# d-ampsch.net
KiCad netlist of a schematic drawn in EAGLE
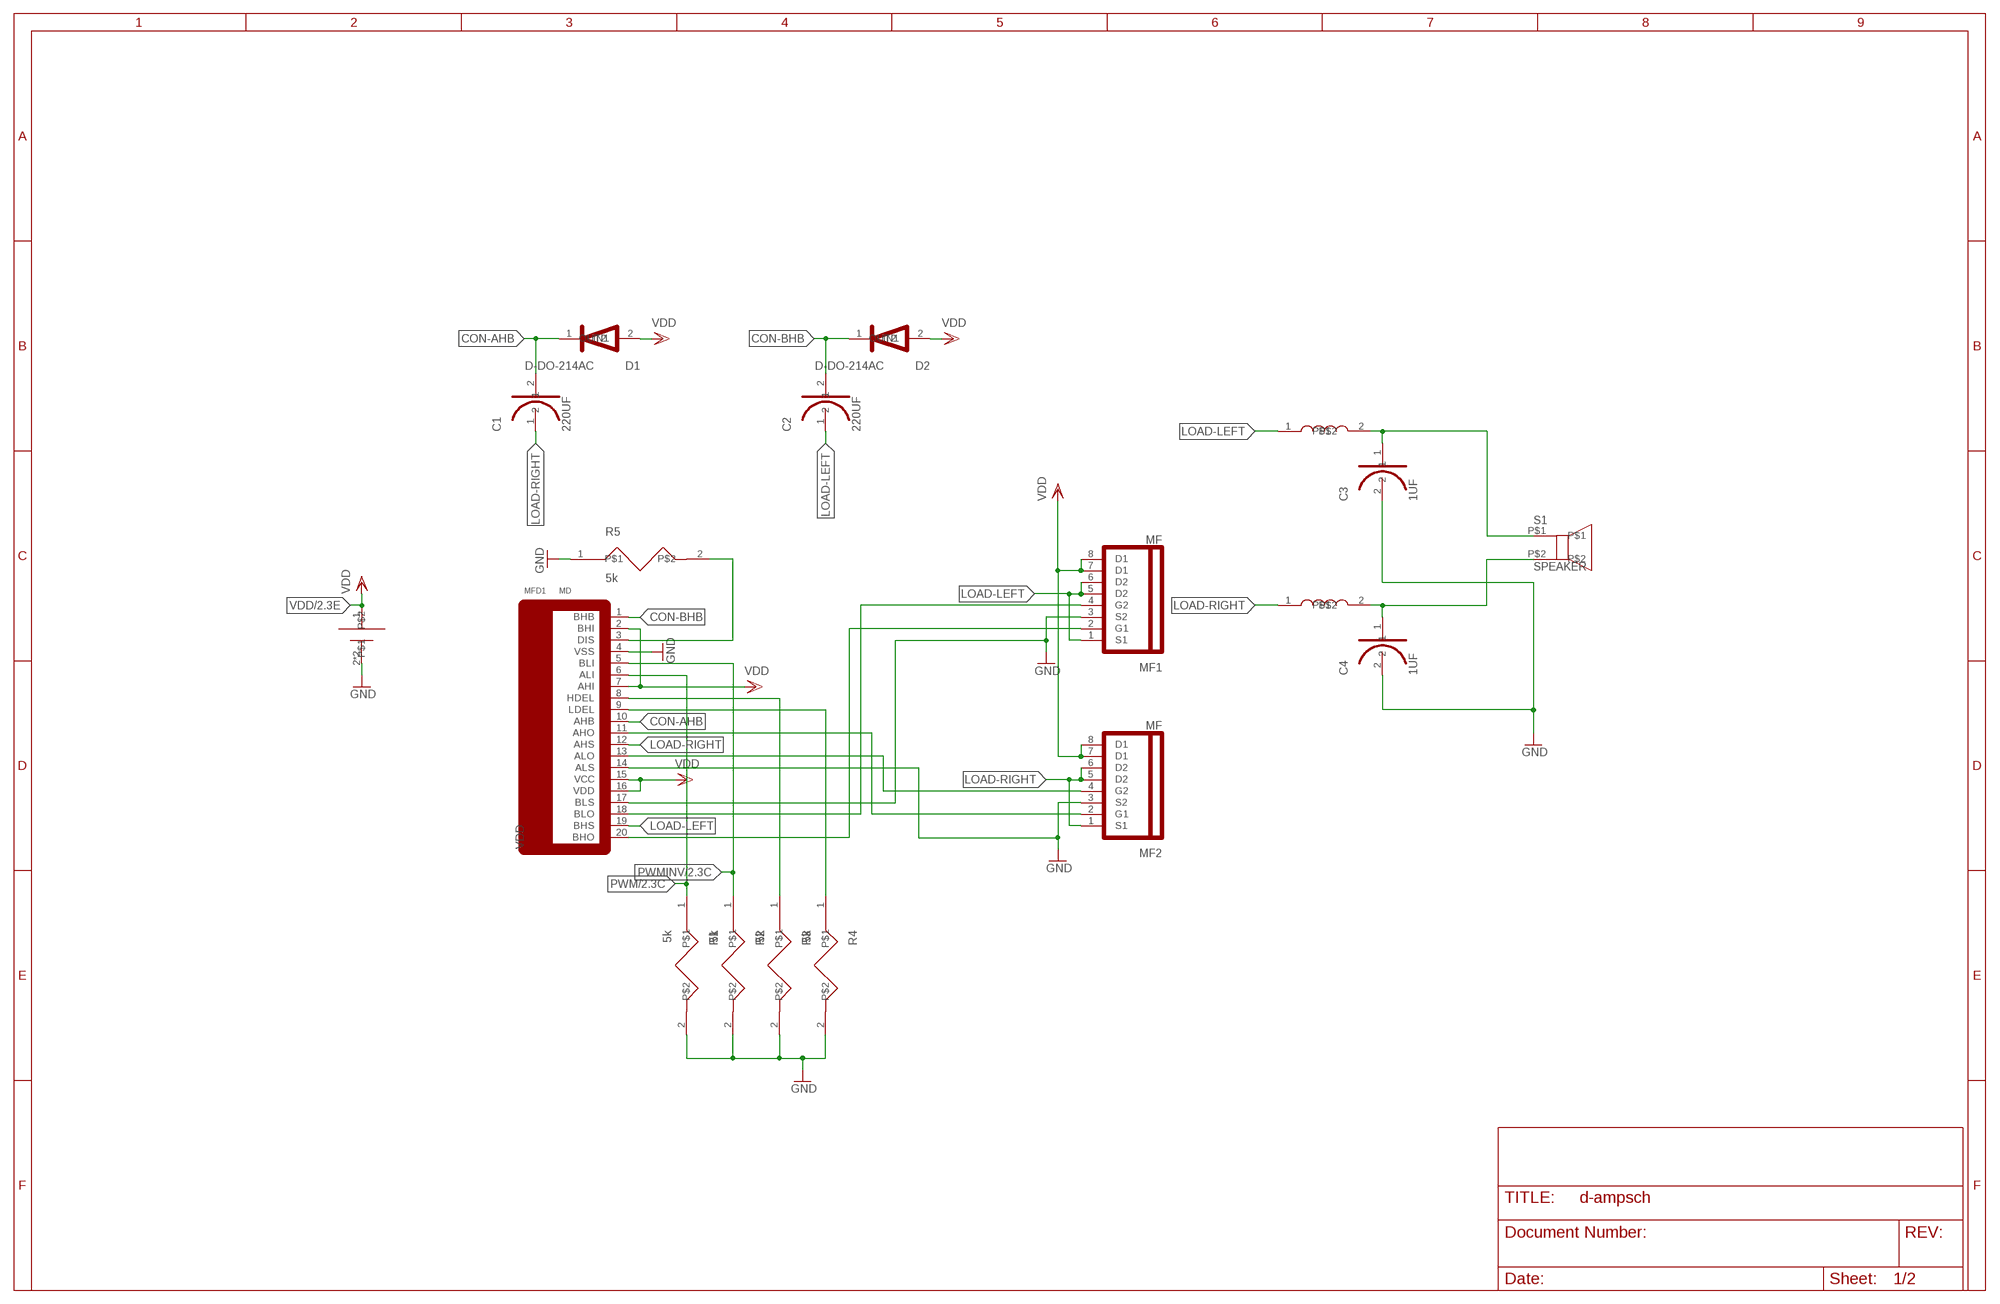
[diagram p0: schematic, sheet 1]
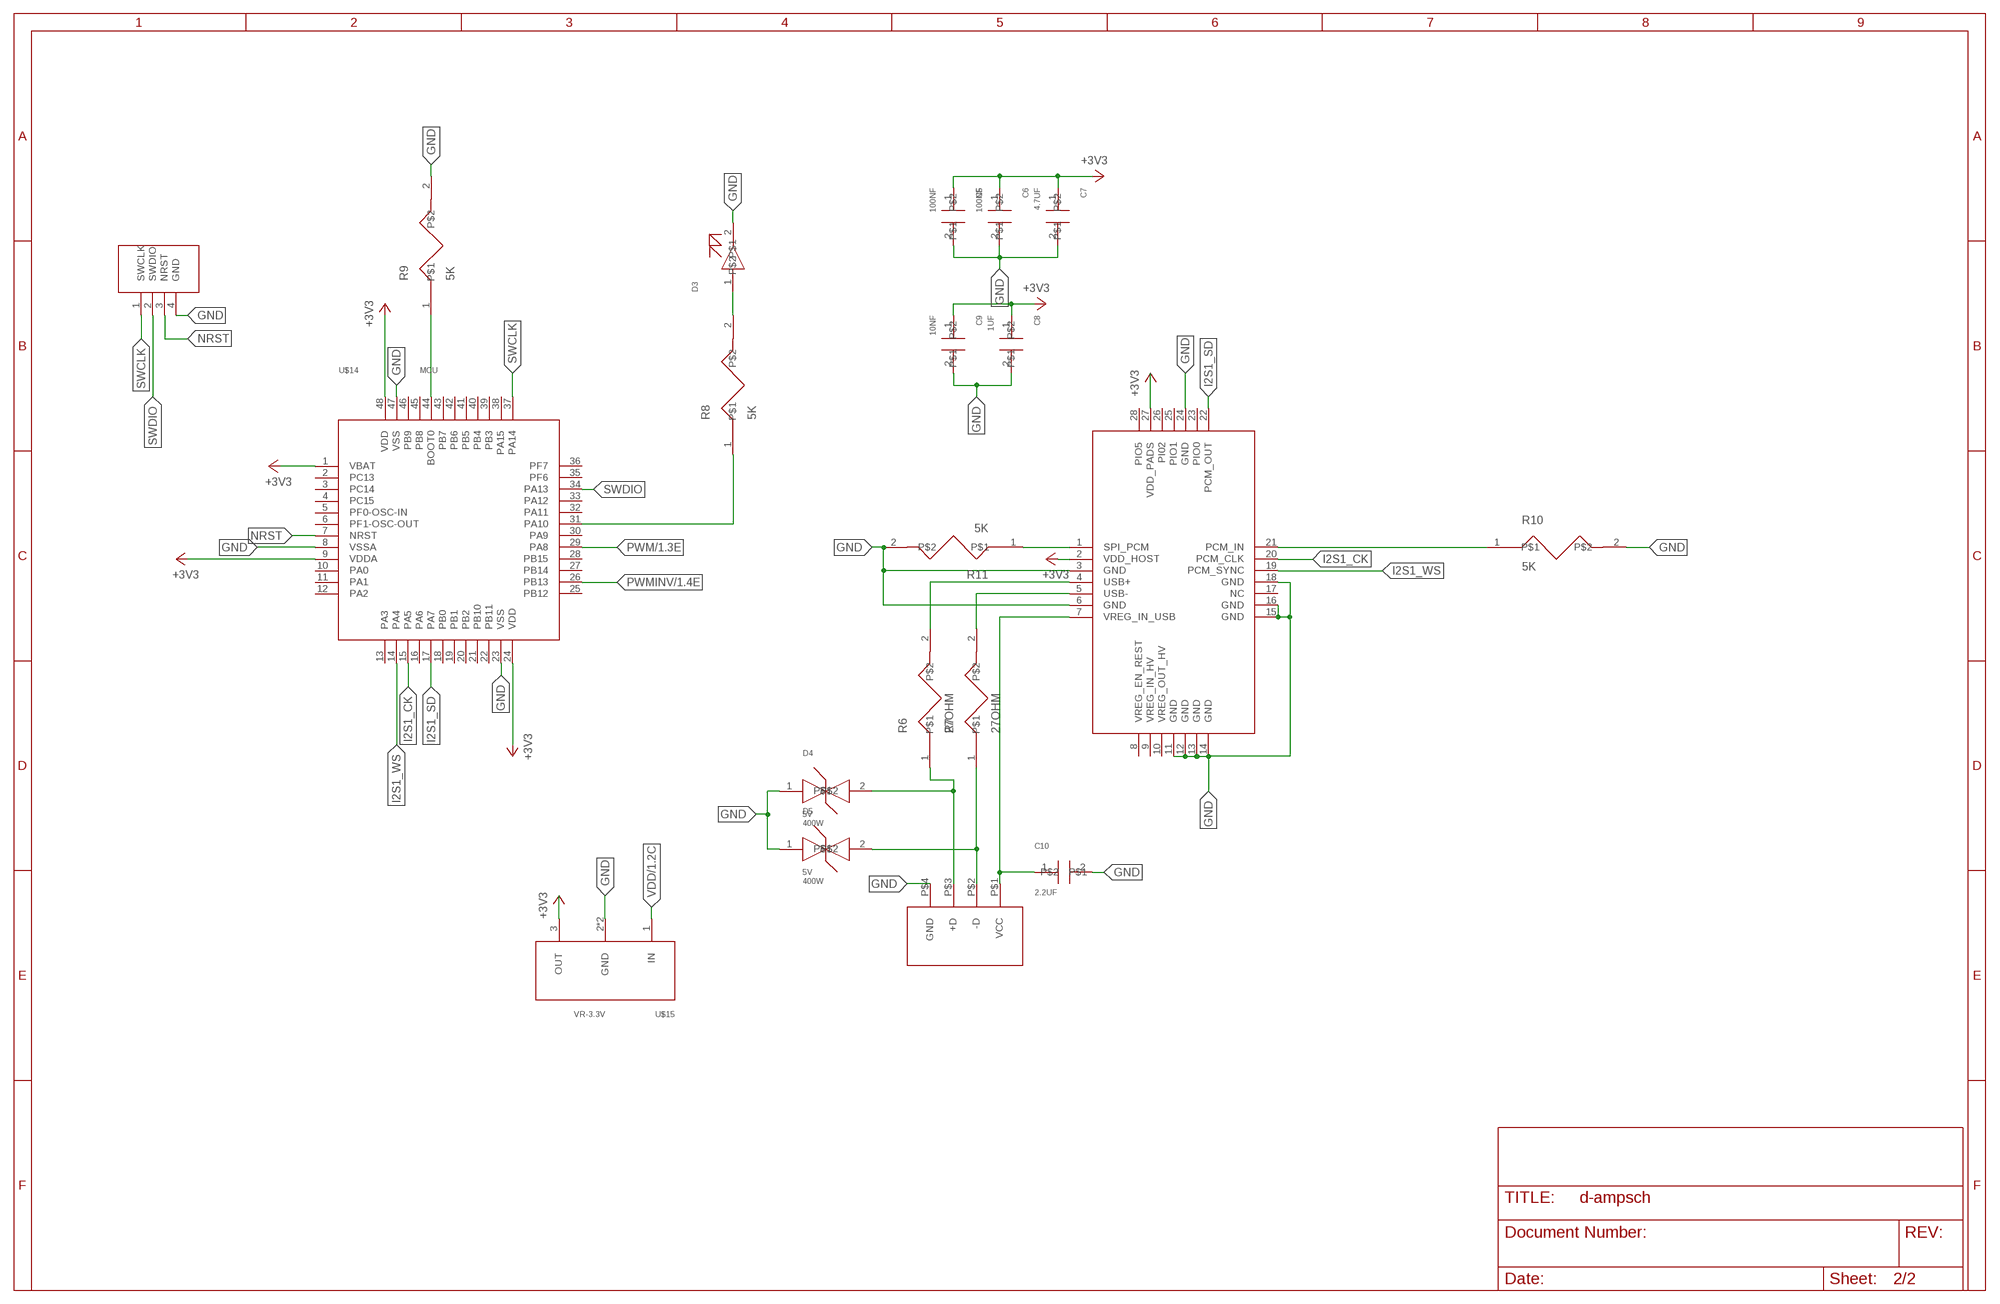
[diagram p1: schematic, sheet 2]

(export (version "E")
  (design (tool "Eeschema 10.0.6"))
  (components
    (comp (ref "C5")
      (value "100NF")
      (footprint "eagle-import:CAPC2012X70N")
      (libsource (lib "eagle-import") (part "C-100NF"))
    )
    (comp (ref "C6")
      (value "100NF")
      (footprint "eagle-import:CAPC2012X70N")
      (libsource (lib "eagle-import") (part "C-100NF"))
    )
    (comp (ref "C7")
      (value "4.7UF")
      (footprint "eagle-import:CAPC2012X145N")
      (libsource (lib "eagle-import") (part "C-4.7UFC-4.7UF"))
    )
    (comp (ref "C8")
      (value "1UF")
      (footprint "eagle-import:CAPC4532X70N")
      (libsource (lib "eagle-import") (part "C-1UF-NPC-1UF-NP"))
    )
    (comp (ref "C9")
      (value "10NF")
      (footprint "eagle-import:CAPC2012X145N")
      (libsource (lib "eagle-import") (part "C-10NF"))
    )
    (comp (ref "C10")
      (value "2.2UF")
      (footprint "eagle-import:CAPC1632X100N")
      (libsource (lib "eagle-import") (part "CAP-2.2UF"))
    )
    (comp (ref "D3")
      (value "LED_GREEN")
      (footprint "eagle-import:LEDC3333X200N")
      (libsource (lib "eagle-import") (part "LED_GREEN"))
    )
    (comp (ref "D4")
      (value "BI-DIR-5V")
      (footprint "eagle-import:DIOM5126X229N")
      (libsource (lib "eagle-import") (part "BI-DIR-5V"))
    )
    (comp (ref "D5")
      (value "BI-DIR-5V")
      (footprint "eagle-import:DIOM5126X229N")
      (libsource (lib "eagle-import") (part "BI-DIR-5V"))
    )
    (comp (ref "R6")
      (value "27OHM")
      (footprint "eagle-import:RESC2012X60N")
      (libsource (lib "eagle-import") (part "R-27OHM"))
    )
    (comp (ref "R7")
      (value "27OHM")
      (footprint "eagle-import:RESC2012X60N")
      (libsource (lib "eagle-import") (part "R-27OHM"))
    )
    (comp (ref "R8")
      (value "5K")
      (footprint "eagle-import:RESC2012X65N")
      (libsource (lib "eagle-import") (part "R-RN73C2A4K99B-5K"))
    )
    (comp (ref "R9")
      (value "5K")
      (footprint "eagle-import:RESC2012X65N")
      (libsource (lib "eagle-import") (part "R-RN73C2A4K99B-5K"))
    )
    (comp (ref "R10")
      (value "5K")
      (footprint "eagle-import:RESC2012X65N")
      (libsource (lib "eagle-import") (part "R-RN73C2A4K99B-5K"))
    )
    (comp (ref "R11")
      (value "5K")
      (footprint "eagle-import:RESC2012X65N")
      (libsource (lib "eagle-import") (part "R-RN73C2A4K99B-5K"))
    )
    (comp (ref "U$13")
      (value "BLUETOOTH")
      (footprint "eagle-import:QFN80P850X1285X175-42N")
      (libsource (lib "eagle-import") (part "BLUETOOTH"))
    )
    (comp (ref "U$14")
      (value "MCU")
      (footprint "eagle-import:QFP50P900X900X160-48N")
      (libsource (lib "eagle-import") (part "MCU"))
    )
    (comp (ref "U$15")
      (value "VR-3.3V")
      (footprint "eagle-import:SOT230P700X175-4N")
      (libsource (lib "eagle-import") (part "VR-3.3V"))
    )
    (comp (ref "U$23")
      (value "USB")
      (footprint "eagle-import:USB")
      (libsource (lib "eagle-import") (part "USB"))
    )
    (comp (ref "U$31")
      (value "PROGRAMCONN")
      (footprint "eagle-import:HDRV4W50P200_1X4_840X220X710B")
      (libsource (lib "eagle-import") (part "PROGRAMCONN"))
    )
    (comp (ref "C1")
      (value "220UF")
      (footprint "eagle-import:CAPAE1030X1050N")
      (libsource (lib "eagle-import") (part "C-EEEFK1H221P-220UF"))
    )
    (comp (ref "C2")
      (value "220UF")
      (footprint "eagle-import:CAPAE1030X1050N")
      (libsource (lib "eagle-import") (part "C-EEEFK1H221P-220UF"))
    )
    (comp (ref "C3")
      (value "1UF")
      (footprint "eagle-import:CAPAE430X610N")
      (libsource (lib "eagle-import") (part "C-EEEHB1H1R0R-1UF"))
    )
    (comp (ref "C4")
      (value "1UF")
      (footprint "eagle-import:CAPAE430X610N")
      (libsource (lib "eagle-import") (part "C-EEEHB1H1R0R-1UF"))
    )
    (comp (ref "D1")
      (value "D-DO-214AC")
      (footprint "eagle-import:SOD5226X220N")
      (libsource (lib "eagle-import") (part "D-DO-214AC"))
    )
    (comp (ref "D2")
      (value "D-DO-214AC")
      (footprint "eagle-import:SOD5226X220N")
      (libsource (lib "eagle-import") (part "D-DO-214AC"))
    )
    (comp (ref "MF1")
      (value "MF")
      (footprint "eagle-import:SOIC127P600X175-8N")
      (libsource (lib "eagle-import") (part "MF-PHN210T"))
    )
    (comp (ref "MF2")
      (value "MF")
      (footprint "eagle-import:SOIC127P600X175-8N")
      (libsource (lib "eagle-import") (part "MF-PHN210T"))
    )
    (comp (ref "MFD1")
      (value "MD")
      (footprint "eagle-import:SOIC127P1032X265-20N")
      (libsource (lib "eagle-import") (part "MD-HIP4081AIBZ"))
    )
    (comp (ref "R1")
      (value "5k")
      (footprint "eagle-import:RESC2012X65N")
      (libsource (lib "eagle-import") (part "R-RN73C2A4K99B-5K"))
    )
    (comp (ref "R2")
      (value "5k")
      (footprint "eagle-import:RESC2012X65N")
      (libsource (lib "eagle-import") (part "R-RN73C2A4K99B-5K"))
    )
    (comp (ref "R3")
      (value "5k")
      (footprint "eagle-import:RESC2012X65N")
      (libsource (lib "eagle-import") (part "R-RN73C2A4K99B-5K"))
    )
    (comp (ref "R4")
      (value "5k")
      (footprint "eagle-import:RESC2012X65N")
      (libsource (lib "eagle-import") (part "R-RN73C2A4K99B-5K"))
    )
    (comp (ref "R5")
      (value "5k")
      (footprint "eagle-import:RESC2012X65N")
      (libsource (lib "eagle-import") (part "R-RN73C2A4K99B-5K"))
    )
    (comp (ref "S1")
      (value "SPEAKER")
      (footprint "eagle-import:SPEAKER")
      (libsource (lib "eagle-import") (part "S-SPEAKER"))
    )
    (comp (ref "U$1")
      (value "B-BATTERYBATTERYCONN")
      (footprint "eagle-import:DIODFN1710X1680X1100-3N")
      (libsource (lib "eagle-import") (part "B-BATTERYBATTERYCONN"))
    )
    (comp (ref "U$21")
      (value "I-WURTH-10UH")
      (footprint "eagle-import:INDDFN2751X2800X1540-3N")
      (libsource (lib "eagle-import") (part "I-WURTH-10UH"))
    )
    (comp (ref "U$22")
      (value "I-WURTH-10UH")
      (footprint "eagle-import:INDDFN2751X2800X1540-3N")
      (libsource (lib "eagle-import") (part "I-WURTH-10UH"))
    )
  )
  (nets
    (net (code "1") (name "+3V3") (class "Default")
      (node (ref "C5") (pin "1") (pinfunction "P$1_1") (pintype "bidirectional"))
      (node (ref "C6") (pin "1") (pinfunction "P$1_1") (pintype "bidirectional"))
      (node (ref "C7") (pin "1") (pinfunction "P$1_1") (pintype "bidirectional"))
      (node (ref "C8") (pin "1") (pinfunction "P$1_1") (pintype "bidirectional"))
      (node (ref "C9") (pin "1") (pinfunction "P$1_1") (pintype "bidirectional"))
      (node (ref "U$13") (pin "2") (pinfunction "VDD_HOST_2") (pintype "bidirectional"))
      (node (ref "U$13") (pin "27") (pinfunction "VDD_PADS_27") (pintype "bidirectional"))
      (node (ref "U$14") (pin "1") (pinfunction "VBAT_1") (pintype "bidirectional"))
      (node (ref "U$14") (pin "24") (pinfunction "VDD_24") (pintype "bidirectional"))
      (node (ref "U$14") (pin "48") (pinfunction "VDD_48") (pintype "bidirectional"))
      (node (ref "U$14") (pin "9") (pinfunction "VDDA_9") (pintype "bidirectional"))
      (node (ref "U$15") (pin "3") (pinfunction "OUT_3") (pintype "bidirectional"))
    )
    (net (code "2") (name "CON-AHB") (class "Default")
      (node (ref "C1") (pin "2") (pinfunction "2_2") (pintype "bidirectional"))
      (node (ref "D1") (pin "1") (pinfunction "IN1_1") (pintype "bidirectional"))
      (node (ref "MFD1") (pin "10") (pinfunction "AHB_10") (pintype "bidirectional"))
    )
    (net (code "3") (name "CON-BHB") (class "Default")
      (node (ref "C2") (pin "2") (pinfunction "2_2") (pintype "bidirectional"))
      (node (ref "D2") (pin "1") (pinfunction "IN1_1") (pintype "bidirectional"))
      (node (ref "MFD1") (pin "1") (pinfunction "BHB_1") (pintype "bidirectional"))
    )
    (net (code "4") (name "GND") (class "Default")
      (node (ref "C10") (pin "2") (pinfunction "P$2_2") (pintype "bidirectional"))
      (node (ref "C3") (pin "2") (pinfunction "1_2") (pintype "bidirectional"))
      (node (ref "C4") (pin "2") (pinfunction "1_2") (pintype "bidirectional"))
      (node (ref "C5") (pin "2") (pinfunction "P$2_2") (pintype "bidirectional"))
      (node (ref "C6") (pin "2") (pinfunction "P$2_2") (pintype "bidirectional"))
      (node (ref "C7") (pin "2") (pinfunction "P$2_2") (pintype "bidirectional"))
      (node (ref "C8") (pin "2") (pinfunction "P$2_2") (pintype "bidirectional"))
      (node (ref "C9") (pin "2") (pinfunction "P$2_2") (pintype "bidirectional"))
      (node (ref "D3") (pin "2") (pinfunction "P$2_2") (pintype "bidirectional"))
      (node (ref "D4") (pin "1") (pinfunction "P$1_1") (pintype "bidirectional"))
      (node (ref "D5") (pin "1") (pinfunction "P$1_1") (pintype "bidirectional"))
      (node (ref "MF1") (pin "3") (pinfunction "S2_3") (pintype "bidirectional"))
      (node (ref "MF2") (pin "3") (pinfunction "S2_3") (pintype "bidirectional"))
      (node (ref "MFD1") (pin "14") (pinfunction "ALS_14") (pintype "bidirectional"))
      (node (ref "MFD1") (pin "17") (pinfunction "BLS_17") (pintype "bidirectional"))
      (node (ref "MFD1") (pin "4") (pinfunction "VSS_4") (pintype "bidirectional"))
      (node (ref "R1") (pin "2") (pinfunction "P$2_2") (pintype "bidirectional"))
      (node (ref "R10") (pin "2") (pinfunction "P$2_2") (pintype "bidirectional"))
      (node (ref "R11") (pin "2") (pinfunction "P$2_2") (pintype "bidirectional"))
      (node (ref "R2") (pin "2") (pinfunction "P$2_2") (pintype "bidirectional"))
      (node (ref "R3") (pin "2") (pinfunction "P$2_2") (pintype "bidirectional"))
      (node (ref "R4") (pin "2") (pinfunction "P$2_2") (pintype "bidirectional"))
      (node (ref "R5") (pin "1") (pinfunction "P$1_1") (pintype "bidirectional"))
      (node (ref "R9") (pin "2") (pinfunction "P$2_2") (pintype "bidirectional"))
      (node (ref "U$1") (pin "2") (pinfunction "P$2_2") (pintype "bidirectional"))
      (node (ref "U$1") (pin "3") (pinfunction "P$2_3") (pintype "bidirectional"))
      (node (ref "U$13") (pin "11") (pinfunction "GND_11") (pintype "bidirectional"))
      (node (ref "U$13") (pin "12") (pinfunction "GND_12") (pintype "bidirectional"))
      (node (ref "U$13") (pin "13") (pinfunction "GND_13") (pintype "bidirectional"))
      (node (ref "U$13") (pin "14") (pinfunction "GND_14") (pintype "bidirectional"))
      (node (ref "U$13") (pin "15") (pinfunction "GND_15") (pintype "bidirectional"))
      (node (ref "U$13") (pin "16") (pinfunction "GND_16") (pintype "bidirectional"))
      (node (ref "U$13") (pin "18") (pinfunction "GND_18") (pintype "bidirectional"))
      (node (ref "U$13") (pin "24") (pinfunction "GND_24") (pintype "bidirectional"))
      (node (ref "U$13") (pin "3") (pinfunction "GND_3") (pintype "bidirectional"))
      (node (ref "U$13") (pin "6") (pinfunction "GND_6") (pintype "bidirectional"))
      (node (ref "U$14") (pin "23") (pinfunction "VSS_23") (pintype "bidirectional"))
      (node (ref "U$14") (pin "47") (pinfunction "VSS_47") (pintype "bidirectional"))
      (node (ref "U$14") (pin "8") (pinfunction "VSSA_8") (pintype "bidirectional"))
      (node (ref "U$15") (pin "2") (pinfunction "GND_2") (pintype "bidirectional"))
      (node (ref "U$15") (pin "4") (pinfunction "GND_4") (pintype "bidirectional"))
      (node (ref "U$23") (pin "P$4") (pinfunction "GND_P$4") (pintype "bidirectional"))
      (node (ref "U$31") (pin "4") (pinfunction "GND_4") (pintype "bidirectional"))
    )
    (net (code "5") (name "I2S1_CK") (class "Default")
      (node (ref "U$13") (pin "20") (pinfunction "PCM_CLK_20") (pintype "bidirectional"))
      (node (ref "U$14") (pin "15") (pinfunction "PA5_15") (pintype "bidirectional"))
    )
    (net (code "6") (name "I2S1_SD") (class "Default")
      (node (ref "U$13") (pin "22") (pinfunction "PCM_OUT_22") (pintype "bidirectional"))
      (node (ref "U$14") (pin "17") (pinfunction "PA7_17") (pintype "bidirectional"))
    )
    (net (code "7") (name "I2S1_WS") (class "Default")
      (node (ref "U$13") (pin "19") (pinfunction "PCM_SYNC_19") (pintype "bidirectional"))
      (node (ref "U$14") (pin "14") (pinfunction "PA4_14") (pintype "bidirectional"))
    )
    (net (code "8") (name "LOAD-LEFT") (class "Default")
      (node (ref "C2") (pin "1") (pinfunction "1_1") (pintype "bidirectional"))
      (node (ref "MF1") (pin "1") (pinfunction "S1_1") (pintype "bidirectional"))
      (node (ref "MF1") (pin "5") (pinfunction "D2_5") (pintype "bidirectional"))
      (node (ref "MF1") (pin "6") (pinfunction "D2_6") (pintype "bidirectional"))
      (node (ref "MFD1") (pin "19") (pinfunction "BHS_19") (pintype "bidirectional"))
      (node (ref "U$21") (pin "1") (pinfunction "P$1_1") (pintype "bidirectional"))
    )
    (net (code "9") (name "LOAD-RIGHT") (class "Default")
      (node (ref "C1") (pin "1") (pinfunction "1_1") (pintype "bidirectional"))
      (node (ref "MF2") (pin "1") (pinfunction "S1_1") (pintype "bidirectional"))
      (node (ref "MF2") (pin "5") (pinfunction "D2_5") (pintype "bidirectional"))
      (node (ref "MF2") (pin "6") (pinfunction "D2_6") (pintype "bidirectional"))
      (node (ref "MFD1") (pin "12") (pinfunction "AHS_12") (pintype "bidirectional"))
      (node (ref "U$22") (pin "1") (pinfunction "P$1_1") (pintype "bidirectional"))
    )
    (net (code "10") (name "NRST") (class "Default")
      (node (ref "U$14") (pin "7") (pinfunction "NRST_7") (pintype "bidirectional"))
      (node (ref "U$31") (pin "3") (pinfunction "NRST_3") (pintype "bidirectional"))
    )
    (net (code "11") (name "Net-(C3-2)") (class "Default")
      (node (ref "C3") (pin "1") (pinfunction "2_1") (pintype "bidirectional"))
      (node (ref "S1") (pin "P$1") (pinfunction "P$1_P$1") (pintype "bidirectional"))
      (node (ref "U$21") (pin "2") (pinfunction "P$2_2") (pintype "bidirectional"))
    )
    (net (code "12") (name "Net-(C4-2)") (class "Default")
      (node (ref "C4") (pin "1") (pinfunction "2_1") (pintype "bidirectional"))
      (node (ref "S1") (pin "P$2") (pinfunction "P$2_P$2") (pintype "bidirectional"))
      (node (ref "U$22") (pin "2") (pinfunction "P$2_2") (pintype "bidirectional"))
    )
    (net (code "13") (name "Net-(C10-P$1)") (class "Default")
      (node (ref "C10") (pin "1") (pinfunction "P$1_1") (pintype "bidirectional"))
      (node (ref "U$13") (pin "7") (pinfunction "VREG_IN_USB_7") (pintype "bidirectional"))
      (node (ref "U$23") (pin "P$1") (pinfunction "VCC_P$1") (pintype "bidirectional"))
    )
    (net (code "14") (name "Net-(D3-P$1)") (class "Default")
      (node (ref "D3") (pin "1") (pinfunction "P$1_1") (pintype "bidirectional"))
      (node (ref "R8") (pin "2") (pinfunction "P$2_2") (pintype "bidirectional"))
    )
    (net (code "15") (name "Net-(D4-P$2)") (class "Default")
      (node (ref "D4") (pin "2") (pinfunction "P$2_2") (pintype "bidirectional"))
      (node (ref "R6") (pin "1") (pinfunction "P$1_1") (pintype "bidirectional"))
      (node (ref "U$23") (pin "P$3") (pinfunction "+D_P$3") (pintype "bidirectional"))
    )
    (net (code "16") (name "Net-(D5-P$2)") (class "Default")
      (node (ref "D5") (pin "2") (pinfunction "P$2_2") (pintype "bidirectional"))
      (node (ref "R7") (pin "1") (pinfunction "P$1_1") (pintype "bidirectional"))
      (node (ref "U$23") (pin "P$2") (pinfunction "-D_P$2") (pintype "bidirectional"))
    )
    (net (code "17") (name "Net-(MF1-G1)") (class "Default")
      (node (ref "MF1") (pin "2") (pinfunction "G1_2") (pintype "bidirectional"))
      (node (ref "MFD1") (pin "20") (pinfunction "BHO_20") (pintype "bidirectional"))
    )
    (net (code "18") (name "Net-(MF1-G2)") (class "Default")
      (node (ref "MF1") (pin "4") (pinfunction "G2_4") (pintype "bidirectional"))
      (node (ref "MFD1") (pin "18") (pinfunction "BLO_18") (pintype "bidirectional"))
    )
    (net (code "19") (name "Net-(MF2-G1)") (class "Default")
      (node (ref "MF2") (pin "2") (pinfunction "G1_2") (pintype "bidirectional"))
      (node (ref "MFD1") (pin "11") (pinfunction "AHO_11") (pintype "bidirectional"))
    )
    (net (code "20") (name "Net-(MF2-G2)") (class "Default")
      (node (ref "MF2") (pin "4") (pinfunction "G2_4") (pintype "bidirectional"))
      (node (ref "MFD1") (pin "13") (pinfunction "ALO_13") (pintype "bidirectional"))
    )
    (net (code "21") (name "Net-(MFD1-DIS)") (class "Default")
      (node (ref "MFD1") (pin "3") (pinfunction "DIS_3") (pintype "bidirectional"))
      (node (ref "R5") (pin "2") (pinfunction "P$2_2") (pintype "bidirectional"))
    )
    (net (code "22") (name "Net-(MFD1-HDEL)") (class "Default")
      (node (ref "MFD1") (pin "8") (pinfunction "HDEL_8") (pintype "bidirectional"))
      (node (ref "R3") (pin "1") (pinfunction "P$1_1") (pintype "bidirectional"))
    )
    (net (code "23") (name "Net-(MFD1-LDEL)") (class "Default")
      (node (ref "MFD1") (pin "9") (pinfunction "LDEL_9") (pintype "bidirectional"))
      (node (ref "R4") (pin "1") (pinfunction "P$1_1") (pintype "bidirectional"))
    )
    (net (code "24") (name "Net-(R6-P$2)") (class "Default")
      (node (ref "R6") (pin "2") (pinfunction "P$2_2") (pintype "bidirectional"))
      (node (ref "U$13") (pin "4") (pinfunction "USB+_4") (pintype "bidirectional"))
    )
    (net (code "25") (name "Net-(R7-P$2)") (class "Default")
      (node (ref "R7") (pin "2") (pinfunction "P$2_2") (pintype "bidirectional"))
      (node (ref "U$13") (pin "5") (pinfunction "USB-_5") (pintype "bidirectional"))
    )
    (net (code "26") (name "Net-(R8-P$1)") (class "Default")
      (node (ref "R8") (pin "1") (pinfunction "P$1_1") (pintype "bidirectional"))
      (node (ref "U$14") (pin "31") (pinfunction "PA10_31") (pintype "bidirectional"))
    )
    (net (code "27") (name "Net-(R9-P$1)") (class "Default")
      (node (ref "R9") (pin "1") (pinfunction "P$1_1") (pintype "bidirectional"))
      (node (ref "U$14") (pin "44") (pinfunction "BOOT0_44") (pintype "bidirectional"))
    )
    (net (code "28") (name "Net-(R10-P$1)") (class "Default")
      (node (ref "R10") (pin "1") (pinfunction "P$1_1") (pintype "bidirectional"))
      (node (ref "U$13") (pin "21") (pinfunction "PCM_IN_21") (pintype "bidirectional"))
    )
    (net (code "29") (name "Net-(R11-P$1)") (class "Default")
      (node (ref "R11") (pin "1") (pinfunction "P$1_1") (pintype "bidirectional"))
      (node (ref "U$13") (pin "1") (pinfunction "SPI_PCM_1") (pintype "bidirectional"))
    )
    (net (code "30") (name "PWM") (class "Default")
      (node (ref "MFD1") (pin "6") (pinfunction "ALI_6") (pintype "bidirectional"))
      (node (ref "R1") (pin "1") (pinfunction "P$1_1") (pintype "bidirectional"))
      (node (ref "U$14") (pin "29") (pinfunction "PA8_29") (pintype "bidirectional"))
    )
    (net (code "31") (name "PWMINV") (class "Default")
      (node (ref "MFD1") (pin "5") (pinfunction "BLI_5") (pintype "bidirectional"))
      (node (ref "R2") (pin "1") (pinfunction "P$1_1") (pintype "bidirectional"))
      (node (ref "U$14") (pin "26") (pinfunction "PB13_26") (pintype "bidirectional"))
    )
    (net (code "32") (name "SWCLK") (class "Default")
      (node (ref "U$14") (pin "37") (pinfunction "PA14_37") (pintype "bidirectional"))
      (node (ref "U$31") (pin "1") (pinfunction "SWCLK_1") (pintype "bidirectional"))
    )
    (net (code "33") (name "SWDIO") (class "Default")
      (node (ref "U$14") (pin "34") (pinfunction "PA13_34") (pintype "bidirectional"))
      (node (ref "U$31") (pin "2") (pinfunction "SWDIO_2") (pintype "bidirectional"))
    )
    (net (code "34") (name "VDD") (class "Default")
      (node (ref "D1") (pin "2") (pinfunction "OUT2_2") (pintype "bidirectional"))
      (node (ref "D2") (pin "2") (pinfunction "OUT2_2") (pintype "bidirectional"))
      (node (ref "MF1") (pin "7") (pinfunction "D1_7") (pintype "bidirectional"))
      (node (ref "MF1") (pin "8") (pinfunction "D1_8") (pintype "bidirectional"))
      (node (ref "MF2") (pin "7") (pinfunction "D1_7") (pintype "bidirectional"))
      (node (ref "MF2") (pin "8") (pinfunction "D1_8") (pintype "bidirectional"))
      (node (ref "MFD1") (pin "15") (pinfunction "VCC_15") (pintype "bidirectional"))
      (node (ref "MFD1") (pin "16") (pinfunction "VDD_16") (pintype "bidirectional"))
      (node (ref "MFD1") (pin "2") (pinfunction "BHI_2") (pintype "bidirectional"))
      (node (ref "MFD1") (pin "7") (pinfunction "AHI_7") (pintype "bidirectional"))
      (node (ref "U$1") (pin "1") (pinfunction "P$1_1") (pintype "bidirectional"))
      (node (ref "U$15") (pin "1") (pinfunction "IN_1") (pintype "bidirectional"))
    )
    (net (code "35") (name "unconnected-(U$13-NC-Pad17)") (class "Default")
      (node (ref "U$13") (pin "17") (pinfunction "NC_17") (pintype "bidirectional"))
    )
    (net (code "36") (name "unconnected-(U$13-PI02-Pad26)") (class "Default")
      (node (ref "U$13") (pin "26") (pinfunction "PI02_26") (pintype "bidirectional"))
    )
    (net (code "37") (name "unconnected-(U$13-PIO0-Pad23)") (class "Default")
      (node (ref "U$13") (pin "23") (pinfunction "PIO0_23") (pintype "bidirectional"))
    )
    (net (code "38") (name "unconnected-(U$13-PIO1-Pad25)") (class "Default")
      (node (ref "U$13") (pin "25") (pinfunction "PIO1_25") (pintype "bidirectional"))
    )
    (net (code "39") (name "unconnected-(U$13-PIO5-Pad28)") (class "Default")
      (node (ref "U$13") (pin "28") (pinfunction "PIO5_28") (pintype "bidirectional"))
    )
    (net (code "40") (name "unconnected-(U$13-VREG_EN_REST-Pad8)") (class "Default")
      (node (ref "U$13") (pin "8") (pinfunction "VREG_EN_REST_8") (pintype "bidirectional"))
    )
    (net (code "41") (name "unconnected-(U$13-VREG_IN_HV-Pad9)") (class "Default")
      (node (ref "U$13") (pin "9") (pinfunction "VREG_IN_HV_9") (pintype "bidirectional"))
    )
    (net (code "42") (name "unconnected-(U$13-VREG_OUT_HV-Pad10)") (class "Default")
      (node (ref "U$13") (pin "10") (pinfunction "VREG_OUT_HV_10") (pintype "bidirectional"))
    )
    (net (code "43") (name "unconnected-(U$14-PA0-Pad10)") (class "Default")
      (node (ref "U$14") (pin "10") (pinfunction "PA0_10") (pintype "bidirectional"))
    )
    (net (code "44") (name "unconnected-(U$14-PA1-Pad11)") (class "Default")
      (node (ref "U$14") (pin "11") (pinfunction "PA1_11") (pintype "bidirectional"))
    )
    (net (code "45") (name "unconnected-(U$14-PA2-Pad12)") (class "Default")
      (node (ref "U$14") (pin "12") (pinfunction "PA2_12") (pintype "bidirectional"))
    )
    (net (code "46") (name "unconnected-(U$14-PA3-Pad13)") (class "Default")
      (node (ref "U$14") (pin "13") (pinfunction "PA3_13") (pintype "bidirectional"))
    )
    (net (code "47") (name "unconnected-(U$14-PA6-Pad16)") (class "Default")
      (node (ref "U$14") (pin "16") (pinfunction "PA6_16") (pintype "bidirectional"))
    )
    (net (code "48") (name "unconnected-(U$14-PA9-Pad30)") (class "Default")
      (node (ref "U$14") (pin "30") (pinfunction "PA9_30") (pintype "bidirectional"))
    )
    (net (code "49") (name "unconnected-(U$14-PA11-Pad32)") (class "Default")
      (node (ref "U$14") (pin "32") (pinfunction "PA11_32") (pintype "bidirectional"))
    )
    (net (code "50") (name "unconnected-(U$14-PA12-Pad33)") (class "Default")
      (node (ref "U$14") (pin "33") (pinfunction "PA12_33") (pintype "bidirectional"))
    )
    (net (code "51") (name "unconnected-(U$14-PA15-Pad38)") (class "Default")
      (node (ref "U$14") (pin "38") (pinfunction "PA15_38") (pintype "bidirectional"))
    )
    (net (code "52") (name "unconnected-(U$14-PB0-Pad18)") (class "Default")
      (node (ref "U$14") (pin "18") (pinfunction "PB0_18") (pintype "bidirectional"))
    )
    (net (code "53") (name "unconnected-(U$14-PB1-Pad19)") (class "Default")
      (node (ref "U$14") (pin "19") (pinfunction "PB1_19") (pintype "bidirectional"))
    )
    (net (code "54") (name "unconnected-(U$14-PB2-Pad20)") (class "Default")
      (node (ref "U$14") (pin "20") (pinfunction "PB2_20") (pintype "bidirectional"))
    )
    (net (code "55") (name "unconnected-(U$14-PB3-Pad39)") (class "Default")
      (node (ref "U$14") (pin "39") (pinfunction "PB3_39") (pintype "bidirectional"))
    )
    (net (code "56") (name "unconnected-(U$14-PB4-Pad40)") (class "Default")
      (node (ref "U$14") (pin "40") (pinfunction "PB4_40") (pintype "bidirectional"))
    )
    (net (code "57") (name "unconnected-(U$14-PB5-Pad41)") (class "Default")
      (node (ref "U$14") (pin "41") (pinfunction "PB5_41") (pintype "bidirectional"))
    )
    (net (code "58") (name "unconnected-(U$14-PB6-Pad42)") (class "Default")
      (node (ref "U$14") (pin "42") (pinfunction "PB6_42") (pintype "bidirectional"))
    )
    (net (code "59") (name "unconnected-(U$14-PB7-Pad43)") (class "Default")
      (node (ref "U$14") (pin "43") (pinfunction "PB7_43") (pintype "bidirectional"))
    )
    (net (code "60") (name "unconnected-(U$14-PB8-Pad45)") (class "Default")
      (node (ref "U$14") (pin "45") (pinfunction "PB8_45") (pintype "bidirectional"))
    )
    (net (code "61") (name "unconnected-(U$14-PB9-Pad46)") (class "Default")
      (node (ref "U$14") (pin "46") (pinfunction "PB9_46") (pintype "bidirectional"))
    )
    (net (code "62") (name "unconnected-(U$14-PB10-Pad21)") (class "Default")
      (node (ref "U$14") (pin "21") (pinfunction "PB10_21") (pintype "bidirectional"))
    )
    (net (code "63") (name "unconnected-(U$14-PB11-Pad22)") (class "Default")
      (node (ref "U$14") (pin "22") (pinfunction "PB11_22") (pintype "bidirectional"))
    )
    (net (code "64") (name "unconnected-(U$14-PB12-Pad25)") (class "Default")
      (node (ref "U$14") (pin "25") (pinfunction "PB12_25") (pintype "bidirectional"))
    )
    (net (code "65") (name "unconnected-(U$14-PB14-Pad27)") (class "Default")
      (node (ref "U$14") (pin "27") (pinfunction "PB14_27") (pintype "bidirectional"))
    )
    (net (code "66") (name "unconnected-(U$14-PB15-Pad28)") (class "Default")
      (node (ref "U$14") (pin "28") (pinfunction "PB15_28") (pintype "bidirectional"))
    )
    (net (code "67") (name "unconnected-(U$14-PC13-Pad2)") (class "Default")
      (node (ref "U$14") (pin "2") (pinfunction "PC13_2") (pintype "bidirectional"))
    )
    (net (code "68") (name "unconnected-(U$14-PC14-Pad3)") (class "Default")
      (node (ref "U$14") (pin "3") (pinfunction "PC14_3") (pintype "bidirectional"))
    )
    (net (code "69") (name "unconnected-(U$14-PC15-Pad4)") (class "Default")
      (node (ref "U$14") (pin "4") (pinfunction "PC15_4") (pintype "bidirectional"))
    )
    (net (code "70") (name "unconnected-(U$14-PF0-OSC-IN-Pad5)") (class "Default")
      (node (ref "U$14") (pin "5") (pinfunction "PF0-OSC-IN_5") (pintype "bidirectional"))
    )
    (net (code "71") (name "unconnected-(U$14-PF1-OSC-OUT-Pad6)") (class "Default")
      (node (ref "U$14") (pin "6") (pinfunction "PF1-OSC-OUT_6") (pintype "bidirectional"))
    )
    (net (code "72") (name "unconnected-(U$14-PF6-Pad35)") (class "Default")
      (node (ref "U$14") (pin "35") (pinfunction "PF6_35") (pintype "bidirectional"))
    )
    (net (code "73") (name "unconnected-(U$14-PF7-Pad36)") (class "Default")
      (node (ref "U$14") (pin "36") (pinfunction "PF7_36") (pintype "bidirectional"))
    )
  )
)
